# CAN-breakout-3_3V-v3.net
KiCad netlist of a schematic drawn in EAGLE
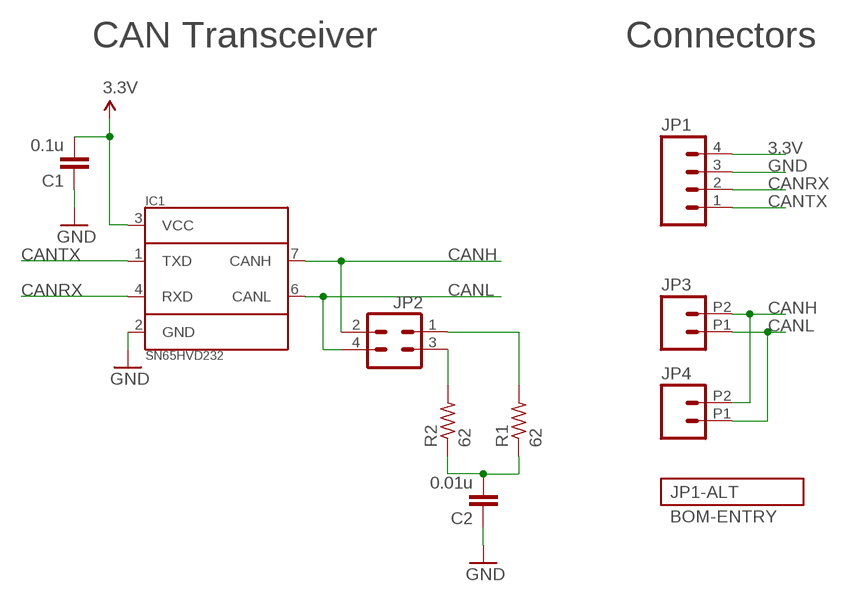
[diagram p0: schematic, sheet 1]

(export (version "E")
  (design (tool "Eeschema 10.0.6"))
  (components
    (comp (ref "C1")
      (value "0.1u")
      (footprint "eagle-import:C1206")
      (fields (field (name "PARTNO") "12065C104KAT2A"))
      (libsource (lib "eagle-import") (part "C-EUC1206"))
    )
    (comp (ref "C2")
      (value "0.01u")
      (footprint "eagle-import:C1206")
      (fields (field (name "PARTNO") "12065C103KAT2A"))
      (libsource (lib "eagle-import") (part "C-EUC1206"))
    )
    (comp (ref "IC1")
      (value "SN65HVD232")
      (footprint "eagle-import:SO8")
      (fields (field (name "PARTNO") "SN65HVD232DR"))
      (libsource (lib "eagle-import") (part "SN65HVD232"))
    )
    (comp (ref "JP1")
      (value "M04PTH")
      (footprint "eagle-import:1X04")
      (fields (field (name "PARTNO") "PREC004SAAN-RC"))
      (libsource (lib "eagle-import") (part "M04PTH"))
    )
    (comp (ref "JP2")
      (value "M02X2")
      (footprint "eagle-import:2X2")
      (fields (field (name "PARTNO") "PREC002DAAN-RC"))
      (libsource (lib "eagle-import") (part "M02X2"))
    )
    (comp (ref "JP3")
      (value "M022.54MM_SCREWTERM")
      (footprint "eagle-import:1X02_2.54_SCREWTERM")
      (fields (field (name "PARTNO") "OSTVN02A150"))
      (libsource (lib "eagle-import") (part "M022.54MM_SCREWTERM"))
    )
    (comp (ref "JP4")
      (value "M022.54MM_SCREWTERM")
      (footprint "eagle-import:1X02_2.54_SCREWTERM")
      (fields (field (name "PARTNO") "OSTVN02A150"))
      (libsource (lib "eagle-import") (part "M022.54MM_SCREWTERM"))
    )
    (comp (ref "R1")
      (value "62")
      (footprint "eagle-import:R1206")
      (fields (field (name "PARTNO") "RC1206FR-0762RL"))
      (libsource (lib "eagle-import") (part "R-US_R1206"))
    )
    (comp (ref "R2")
      (value "62")
      (footprint "eagle-import:R1206")
      (fields (field (name "PARTNO") "RC1206FR-0762RL"))
      (libsource (lib "eagle-import") (part "R-US_R1206"))
    )
  )
  (nets
    (net (code "1") (name "/CANH") (class "Default")
      (node (ref "IC1") (pin "7") (pinfunction "CANH_7") (pintype "bidirectional"))
      (node (ref "JP2") (pin "2") (pinfunction "2_2") (pintype "passive"))
      (node (ref "JP3") (pin "P2") (pinfunction "2_P2") (pintype "passive"))
      (node (ref "JP4") (pin "P2") (pinfunction "2_P2") (pintype "passive"))
    )
    (net (code "2") (name "/CANL") (class "Default")
      (node (ref "IC1") (pin "6") (pinfunction "CANL_6") (pintype "bidirectional"))
      (node (ref "JP2") (pin "4") (pinfunction "4_4") (pintype "passive"))
      (node (ref "JP3") (pin "P1") (pinfunction "1_P1") (pintype "passive"))
      (node (ref "JP4") (pin "P1") (pinfunction "1_P1") (pintype "passive"))
    )
    (net (code "3") (name "/CANRX") (class "Default")
      (node (ref "IC1") (pin "4") (pinfunction "RXD_4") (pintype "bidirectional"))
      (node (ref "JP1") (pin "2") (pinfunction "2_2") (pintype "passive"))
    )
    (net (code "4") (name "/CANTX") (class "Default")
      (node (ref "IC1") (pin "1") (pinfunction "TXD_1") (pintype "bidirectional"))
      (node (ref "JP1") (pin "1") (pinfunction "1_1") (pintype "passive"))
    )
    (net (code "5") (name "3.3V") (class "Default")
      (node (ref "C1") (pin "2") (pinfunction "2_2") (pintype "passive"))
      (node (ref "IC1") (pin "3") (pinfunction "VCC_3") (pintype "bidirectional"))
      (node (ref "JP1") (pin "4") (pinfunction "4_4") (pintype "passive"))
    )
    (net (code "6") (name "GND") (class "Default")
      (node (ref "C1") (pin "1") (pinfunction "1_1") (pintype "passive"))
      (node (ref "C2") (pin "1") (pinfunction "1_1") (pintype "passive"))
      (node (ref "IC1") (pin "2") (pinfunction "GND_2") (pintype "bidirectional"))
      (node (ref "JP1") (pin "3") (pinfunction "3_3") (pintype "passive"))
    )
    (net (code "7") (name "Net-(C2-Pad2)") (class "Default")
      (node (ref "C2") (pin "2") (pinfunction "2_2") (pintype "passive"))
      (node (ref "R1") (pin "1") (pinfunction "1_1") (pintype "passive"))
      (node (ref "R2") (pin "1") (pinfunction "1_1") (pintype "passive"))
    )
    (net (code "8") (name "Net-(JP2-Pad1)") (class "Default")
      (node (ref "JP2") (pin "1") (pinfunction "1_1") (pintype "passive"))
      (node (ref "R1") (pin "2") (pinfunction "2_2") (pintype "passive"))
    )
    (net (code "9") (name "Net-(JP2-Pad3)") (class "Default")
      (node (ref "JP2") (pin "3") (pinfunction "3_3") (pintype "passive"))
      (node (ref "R2") (pin "2") (pinfunction "2_2") (pintype "passive"))
    )
  )
)
